# Power_Distribution.net
KiCad netlist of a schematic drawn in EAGLE
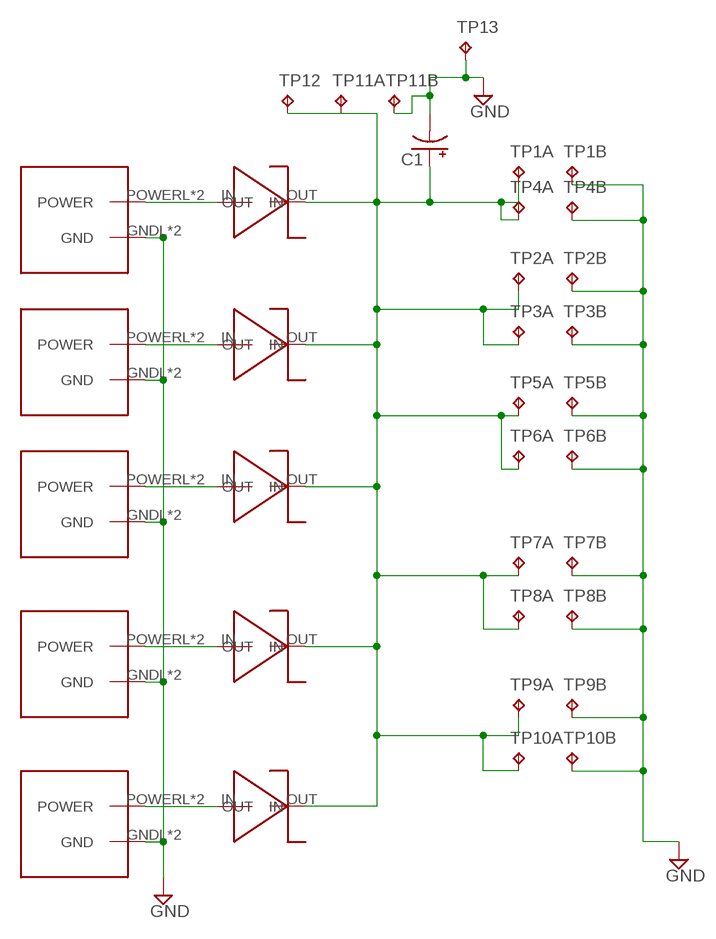
[diagram p0: schematic, sheet 1]

(export (version "E")
  (design (tool "Eeschema 10.0.6"))
  (components
    (comp (ref "C1")
      (value "CPOL-USE2.5-6")
      (footprint "eagle-import:E2,5-6")
      (libsource (lib "eagle-import") (part "CPOL-USE2.5-6"))
    )
    (comp (ref "TP1")
      (value "TP2P2-38-17")
      (footprint "eagle-import:P2-38-17")
      (libsource (lib "eagle-import") (part "TP2P2-38-17"))
    )
    (comp (ref "TP2")
      (value "TP2P2-38-17")
      (footprint "eagle-import:P2-38-17")
      (libsource (lib "eagle-import") (part "TP2P2-38-17"))
    )
    (comp (ref "TP3")
      (value "TP2P2-38-17")
      (footprint "eagle-import:P2-38-17")
      (libsource (lib "eagle-import") (part "TP2P2-38-17"))
    )
    (comp (ref "TP4")
      (value "TP2P2-38-17")
      (footprint "eagle-import:P2-38-17")
      (libsource (lib "eagle-import") (part "TP2P2-38-17"))
    )
    (comp (ref "TP5")
      (value "TP2P2-38-17")
      (footprint "eagle-import:P2-38-17")
      (libsource (lib "eagle-import") (part "TP2P2-38-17"))
    )
    (comp (ref "TP6")
      (value "TP2P2-38-17")
      (footprint "eagle-import:P2-38-17")
      (libsource (lib "eagle-import") (part "TP2P2-38-17"))
    )
    (comp (ref "TP7")
      (value "TP2P2-38-17")
      (footprint "eagle-import:P2-38-17")
      (libsource (lib "eagle-import") (part "TP2P2-38-17"))
    )
    (comp (ref "TP8")
      (value "TP2P2-38-17")
      (footprint "eagle-import:P2-38-17")
      (libsource (lib "eagle-import") (part "TP2P2-38-17"))
    )
    (comp (ref "TP9")
      (value "TP2P2-38-17")
      (footprint "eagle-import:P2-38-17")
      (libsource (lib "eagle-import") (part "TP2P2-38-17"))
    )
    (comp (ref "TP10")
      (value "TP2P2-38-17")
      (footprint "eagle-import:P2-38-17")
      (libsource (lib "eagle-import") (part "TP2P2-38-17"))
    )
    (comp (ref "TP11")
      (value "TP2P2-38-17")
      (footprint "eagle-import:P2-38-17")
      (libsource (lib "eagle-import") (part "TP2P2-38-17"))
    )
    (comp (ref "TP12")
      (value "TPTP20SQ")
      (footprint "eagle-import:TP20SQ")
      (libsource (lib "eagle-import") (part "TPTP20SQ"))
    )
    (comp (ref "TP13")
      (value "TPTP20SQ")
      (footprint "eagle-import:TP20SQ")
      (libsource (lib "eagle-import") (part "TPTP20SQ"))
    )
    (comp (ref "U$1")
      (value "2X2-MOLEX")
      (footprint "eagle-import:2X2MOLEX")
      (libsource (lib "eagle-import") (part "2X2-MOLEX"))
    )
    (comp (ref "U$2")
      (value "2X2-MOLEX")
      (footprint "eagle-import:2X2MOLEX")
      (libsource (lib "eagle-import") (part "2X2-MOLEX"))
    )
    (comp (ref "U$3")
      (value "2X2-MOLEX")
      (footprint "eagle-import:2X2MOLEX")
      (libsource (lib "eagle-import") (part "2X2-MOLEX"))
    )
    (comp (ref "U$4")
      (value "2X2-MOLEX")
      (footprint "eagle-import:2X2MOLEX")
      (libsource (lib "eagle-import") (part "2X2-MOLEX"))
    )
    (comp (ref "U$5")
      (value "2X2-MOLEX")
      (footprint "eagle-import:2X2MOLEX")
      (libsource (lib "eagle-import") (part "2X2-MOLEX"))
    )
    (comp (ref "U$6")
      (value "DO-214AB")
      (footprint "eagle-import:DO-214AB")
      (libsource (lib "eagle-import") (part "DO-214AB"))
    )
    (comp (ref "U$7")
      (value "DO-214AB")
      (footprint "eagle-import:DO-214AB")
      (libsource (lib "eagle-import") (part "DO-214AB"))
    )
    (comp (ref "U$8")
      (value "DO-214AB")
      (footprint "eagle-import:DO-214AB")
      (libsource (lib "eagle-import") (part "DO-214AB"))
    )
    (comp (ref "U$9")
      (value "DO-214AB")
      (footprint "eagle-import:DO-214AB")
      (libsource (lib "eagle-import") (part "DO-214AB"))
    )
    (comp (ref "U$10")
      (value "DO-214AB")
      (footprint "eagle-import:DO-214AB")
      (libsource (lib "eagle-import") (part "DO-214AB"))
    )
  )
  (nets
    (net (code "1") (name "GND") (class "Default")
      (node (ref "C1") (pin "-") (pinfunction "-_-") (pintype "passive"))
      (node (ref "TP1") (pin "TP-2") (pinfunction "TP_TP-2") (pintype "input"))
      (node (ref "TP10") (pin "TP-2") (pinfunction "TP_TP-2") (pintype "input"))
      (node (ref "TP11") (pin "TP-2") (pinfunction "TP_TP-2") (pintype "input"))
      (node (ref "TP13") (pin "TP") (pinfunction "TP_TP") (pintype "input"))
      (node (ref "TP2") (pin "TP-2") (pinfunction "TP_TP-2") (pintype "input"))
      (node (ref "TP3") (pin "TP-2") (pinfunction "TP_TP-2") (pintype "input"))
      (node (ref "TP4") (pin "TP-2") (pinfunction "TP_TP-2") (pintype "input"))
      (node (ref "TP5") (pin "TP-2") (pinfunction "TP_TP-2") (pintype "input"))
      (node (ref "TP6") (pin "TP-2") (pinfunction "TP_TP-2") (pintype "input"))
      (node (ref "TP7") (pin "TP-2") (pinfunction "TP_TP-2") (pintype "input"))
      (node (ref "TP8") (pin "TP-2") (pinfunction "TP_TP-2") (pintype "input"))
      (node (ref "TP9") (pin "TP-2") (pinfunction "TP_TP-2") (pintype "input"))
      (node (ref "U$1") (pin "GNDL") (pinfunction "GND_GNDL") (pintype "bidirectional"))
      (node (ref "U$1") (pin "GNDR") (pinfunction "GND_GNDR") (pintype "bidirectional"))
      (node (ref "U$2") (pin "GNDL") (pinfunction "GND_GNDL") (pintype "bidirectional"))
      (node (ref "U$2") (pin "GNDR") (pinfunction "GND_GNDR") (pintype "bidirectional"))
      (node (ref "U$3") (pin "GNDL") (pinfunction "GND_GNDL") (pintype "bidirectional"))
      (node (ref "U$3") (pin "GNDR") (pinfunction "GND_GNDR") (pintype "bidirectional"))
      (node (ref "U$4") (pin "GNDL") (pinfunction "GND_GNDL") (pintype "bidirectional"))
      (node (ref "U$4") (pin "GNDR") (pinfunction "GND_GNDR") (pintype "bidirectional"))
      (node (ref "U$5") (pin "GNDL") (pinfunction "GND_GNDL") (pintype "bidirectional"))
      (node (ref "U$5") (pin "GNDR") (pinfunction "GND_GNDR") (pintype "bidirectional"))
    )
    (net (code "2") (name "Net-(TP10A-TP)") (class "Default")
      (node (ref "C1") (pin "+") (pinfunction "+_+") (pintype "passive"))
      (node (ref "TP1") (pin "TP-1") (pinfunction "TP_TP-1") (pintype "input"))
      (node (ref "TP10") (pin "TP-1") (pinfunction "TP_TP-1") (pintype "input"))
      (node (ref "TP11") (pin "TP-1") (pinfunction "TP_TP-1") (pintype "input"))
      (node (ref "TP12") (pin "TP") (pinfunction "TP_TP") (pintype "input"))
      (node (ref "TP2") (pin "TP-1") (pinfunction "TP_TP-1") (pintype "input"))
      (node (ref "TP3") (pin "TP-1") (pinfunction "TP_TP-1") (pintype "input"))
      (node (ref "TP4") (pin "TP-1") (pinfunction "TP_TP-1") (pintype "input"))
      (node (ref "TP5") (pin "TP-1") (pinfunction "TP_TP-1") (pintype "input"))
      (node (ref "TP6") (pin "TP-1") (pinfunction "TP_TP-1") (pintype "input"))
      (node (ref "TP7") (pin "TP-1") (pinfunction "TP_TP-1") (pintype "input"))
      (node (ref "TP8") (pin "TP-1") (pinfunction "TP_TP-1") (pintype "input"))
      (node (ref "TP9") (pin "TP-1") (pinfunction "TP_TP-1") (pintype "input"))
      (node (ref "U$10") (pin "OUT") (pinfunction "OUT_OUT") (pintype "bidirectional"))
      (node (ref "U$6") (pin "OUT") (pinfunction "OUT_OUT") (pintype "bidirectional"))
      (node (ref "U$7") (pin "OUT") (pinfunction "OUT_OUT") (pintype "bidirectional"))
      (node (ref "U$8") (pin "OUT") (pinfunction "OUT_OUT") (pintype "bidirectional"))
      (node (ref "U$9") (pin "OUT") (pinfunction "OUT_OUT") (pintype "bidirectional"))
    )
    (net (code "3") (name "Net-(U$1-POWER-PadPOWERL)") (class "Default")
      (node (ref "U$1") (pin "POWERL") (pinfunction "POWER_POWERL") (pintype "bidirectional"))
      (node (ref "U$1") (pin "POWERR") (pinfunction "POWER_POWERR") (pintype "bidirectional"))
      (node (ref "U$7") (pin "IN") (pinfunction "IN_IN") (pintype "bidirectional"))
    )
    (net (code "4") (name "Net-(U$2-POWER-PadPOWERL)") (class "Default")
      (node (ref "U$2") (pin "POWERL") (pinfunction "POWER_POWERL") (pintype "bidirectional"))
      (node (ref "U$2") (pin "POWERR") (pinfunction "POWER_POWERR") (pintype "bidirectional"))
      (node (ref "U$8") (pin "IN") (pinfunction "IN_IN") (pintype "bidirectional"))
    )
    (net (code "5") (name "Net-(U$3-POWER-PadPOWERL)") (class "Default")
      (node (ref "U$3") (pin "POWERL") (pinfunction "POWER_POWERL") (pintype "bidirectional"))
      (node (ref "U$3") (pin "POWERR") (pinfunction "POWER_POWERR") (pintype "bidirectional"))
      (node (ref "U$9") (pin "IN") (pinfunction "IN_IN") (pintype "bidirectional"))
    )
    (net (code "6") (name "Net-(U$5-POWER-PadPOWERL)") (class "Default")
      (node (ref "U$5") (pin "POWERL") (pinfunction "POWER_POWERL") (pintype "bidirectional"))
      (node (ref "U$5") (pin "POWERR") (pinfunction "POWER_POWERR") (pintype "bidirectional"))
      (node (ref "U$6") (pin "IN") (pinfunction "IN_IN") (pintype "bidirectional"))
    )
    (net (code "7") (name "Net-(U$10-PadIN)") (class "Default")
      (node (ref "U$10") (pin "IN") (pinfunction "IN_IN") (pintype "bidirectional"))
      (node (ref "U$4") (pin "POWERL") (pinfunction "POWER_POWERL") (pintype "bidirectional"))
      (node (ref "U$4") (pin "POWERR") (pinfunction "POWER_POWERR") (pintype "bidirectional"))
    )
  )
)
